# LinCorrector4.net
KiCad netlist of a schematic drawn in EAGLE
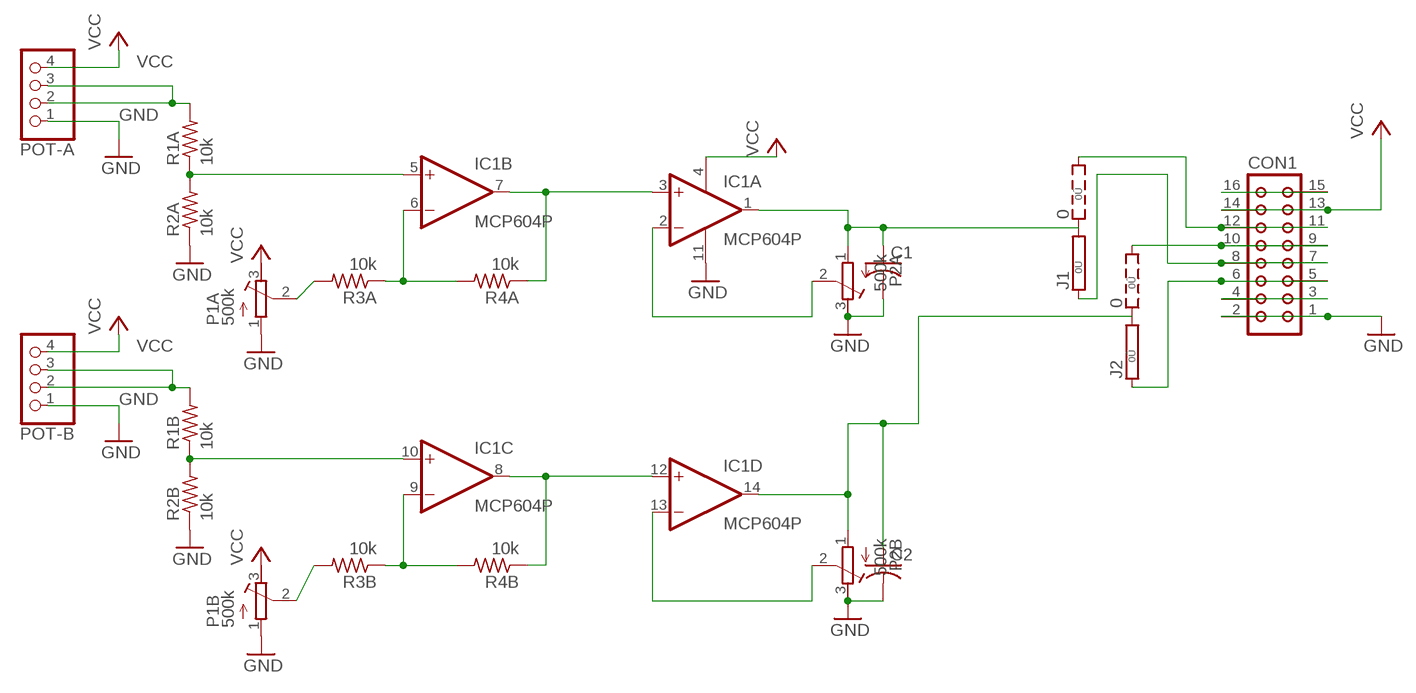
[diagram p0: schematic, sheet 1]

(export (version "E")
  (design (tool "Eeschema 10.0.6"))
  (components
    (comp (ref "C1")
      (value "C-US050-030X075")
      (footprint "eagle-import:C050-030X075")
      (libsource (lib "eagle-import") (part "C-US050-030X075"))
    )
    (comp (ref "C2")
      (value "C-US050-030X075")
      (footprint "eagle-import:C050-030X075")
      (libsource (lib "eagle-import") (part "C-US050-030X075"))
    )
    (comp (ref "CON1")
      (value "CON16")
      (footprint "eagle-import:CON16")
      (libsource (lib "eagle-import") (part "CON16"))
    )
    (comp (ref "IC1")
      (value "MCP604P")
      (footprint "eagle-import:DIL14")
      (libsource (lib "eagle-import") (part "MCP604P"))
    )
    (comp (ref "J1")
      (value "0")
      (footprint "eagle-import:0R2_10")
      (libsource (lib "eagle-import") (part "0R2"))
    )
    (comp (ref "J2")
      (value "0")
      (footprint "eagle-import:0R2_10")
      (libsource (lib "eagle-import") (part "0R2"))
    )
    (comp (ref "P1A")
      (value "500k")
      (footprint "eagle-import:RTRIM3296W")
      (libsource (lib "eagle-import") (part "R-TRIMM3296W"))
    )
    (comp (ref "P1B")
      (value "500k")
      (footprint "eagle-import:RTRIM3296W")
      (libsource (lib "eagle-import") (part "R-TRIMM3296W"))
    )
    (comp (ref "P2A")
      (value "500k")
      (footprint "eagle-import:RTRIM3296W")
      (libsource (lib "eagle-import") (part "R-TRIMM3296W"))
    )
    (comp (ref "P2B")
      (value "500k")
      (footprint "eagle-import:RTRIM3296W")
      (libsource (lib "eagle-import") (part "R-TRIMM3296W"))
    )
    (comp (ref "POT-A")
      (value "PINHD-1X4/90")
      (footprint "eagle-import:1X04_90")
      (libsource (lib "eagle-import") (part "PINHD-1X4/90"))
    )
    (comp (ref "POT-B")
      (value "PINHD-1X4/90")
      (footprint "eagle-import:1X04_90")
      (libsource (lib "eagle-import") (part "PINHD-1X4/90"))
    )
    (comp (ref "R1A")
      (value "10k")
      (footprint "eagle-import:0204_7")
      (libsource (lib "eagle-import") (part "R-US_0204/7"))
    )
    (comp (ref "R1B")
      (value "10k")
      (footprint "eagle-import:0204_7")
      (libsource (lib "eagle-import") (part "R-US_0204/7"))
    )
    (comp (ref "R2A")
      (value "10k")
      (footprint "eagle-import:0204_7")
      (libsource (lib "eagle-import") (part "R-US_0204/7"))
    )
    (comp (ref "R2B")
      (value "10k")
      (footprint "eagle-import:0204_7")
      (libsource (lib "eagle-import") (part "R-US_0204/7"))
    )
    (comp (ref "R3A")
      (value "10k")
      (footprint "eagle-import:0204_7")
      (libsource (lib "eagle-import") (part "R-US_0204/7"))
    )
    (comp (ref "R3B")
      (value "10k")
      (footprint "eagle-import:0204_7")
      (libsource (lib "eagle-import") (part "R-US_0204/7"))
    )
    (comp (ref "R4A")
      (value "10k")
      (footprint "eagle-import:0204_7")
      (libsource (lib "eagle-import") (part "R-US_0204/7"))
    )
    (comp (ref "R4B")
      (value "10k")
      (footprint "eagle-import:0204_7")
      (libsource (lib "eagle-import") (part "R-US_0204/7"))
    )
  )
  (nets
    (net (code "1") (name "GND") (class "Default")
      (node (ref "C1") (pin "2") (pinfunction "2_2") (pintype "passive"))
      (node (ref "C2") (pin "2") (pinfunction "2_2") (pintype "passive"))
      (node (ref "CON1") (pin "1") (pinfunction "1_1") (pintype "passive"))
      (node (ref "CON1") (pin "2") (pinfunction "2_2") (pintype "passive"))
      (node (ref "IC1") (pin "11") (pinfunction "V-_11") (pintype "power_in"))
      (node (ref "P1A") (pin "1") (pinfunction "A_1") (pintype "passive"))
      (node (ref "P1B") (pin "1") (pinfunction "A_1") (pintype "passive"))
      (node (ref "P2A") (pin "3") (pinfunction "E_3") (pintype "passive"))
      (node (ref "P2B") (pin "3") (pinfunction "E_3") (pintype "passive"))
      (node (ref "POT-A") (pin "1") (pinfunction "1_1") (pintype "passive"))
      (node (ref "POT-B") (pin "1") (pinfunction "1_1") (pintype "passive"))
      (node (ref "R2A") (pin "1") (pinfunction "1_1") (pintype "passive"))
      (node (ref "R2B") (pin "1") (pinfunction "1_1") (pintype "passive"))
    )
    (net (code "2") (name "Net-(CON1-Pad3)") (class "Default")
      (node (ref "CON1") (pin "3") (pinfunction "3_3") (pintype "passive"))
      (node (ref "CON1") (pin "4") (pinfunction "4_4") (pintype "passive"))
    )
    (net (code "3") (name "Net-(CON1-Pad5)") (class "Default")
      (node (ref "CON1") (pin "5") (pinfunction "5_5") (pintype "passive"))
      (node (ref "CON1") (pin "6") (pinfunction "6_6") (pintype "passive"))
      (node (ref "J2") (pin "1") (pinfunction "1_1") (pintype "passive"))
    )
    (net (code "4") (name "Net-(CON1-Pad7)") (class "Default")
      (node (ref "CON1") (pin "7") (pinfunction "7_7") (pintype "passive"))
      (node (ref "CON1") (pin "8") (pinfunction "8_8") (pintype "passive"))
      (node (ref "J1") (pin "1") (pinfunction "1_1") (pintype "passive"))
    )
    (net (code "5") (name "Net-(CON1-Pad10)") (class "Default")
      (node (ref "CON1") (pin "10") (pinfunction "10_10") (pintype "passive"))
      (node (ref "CON1") (pin "9") (pinfunction "9_9") (pintype "passive"))
      (node (ref "J2") (pin "3") (pinfunction "3_3") (pintype "passive"))
    )
    (net (code "6") (name "Net-(CON1-Pad11)") (class "Default")
      (node (ref "CON1") (pin "11") (pinfunction "11_11") (pintype "passive"))
      (node (ref "CON1") (pin "12") (pinfunction "12_12") (pintype "passive"))
      (node (ref "J1") (pin "3") (pinfunction "3_3") (pintype "passive"))
    )
    (net (code "7") (name "Net-(CON1-Pad15)") (class "Default")
      (node (ref "CON1") (pin "15") (pinfunction "15_15") (pintype "passive"))
      (node (ref "CON1") (pin "16") (pinfunction "16_16") (pintype "passive"))
    )
    (net (code "8") (name "Net-(IC1A-+IN)") (class "Default")
      (node (ref "IC1") (pin "3") (pinfunction "+IN_3") (pintype "input"))
      (node (ref "IC1") (pin "7") (pinfunction "OUT_7") (pintype "output"))
      (node (ref "R4A") (pin "1") (pinfunction "1_1") (pintype "passive"))
    )
    (net (code "9") (name "Net-(IC1A--IN)") (class "Default")
      (node (ref "IC1") (pin "2") (pinfunction "-IN_2") (pintype "input"))
      (node (ref "P2A") (pin "2") (pinfunction "S_2") (pintype "passive"))
    )
    (net (code "10") (name "Net-(IC1A-OUT)") (class "Default")
      (node (ref "C1") (pin "1") (pinfunction "1_1") (pintype "passive"))
      (node (ref "IC1") (pin "1") (pinfunction "OUT_1") (pintype "output"))
      (node (ref "J1") (pin "2") (pinfunction "2_2") (pintype "passive"))
      (node (ref "P2A") (pin "1") (pinfunction "A_1") (pintype "passive"))
    )
    (net (code "11") (name "Net-(IC1B-+IN)") (class "Default")
      (node (ref "IC1") (pin "5") (pinfunction "+IN_5") (pintype "input"))
      (node (ref "R1A") (pin "1") (pinfunction "1_1") (pintype "passive"))
      (node (ref "R2A") (pin "2") (pinfunction "2_2") (pintype "passive"))
    )
    (net (code "12") (name "Net-(IC1B--IN)") (class "Default")
      (node (ref "IC1") (pin "6") (pinfunction "-IN_6") (pintype "input"))
      (node (ref "R3A") (pin "1") (pinfunction "1_1") (pintype "passive"))
      (node (ref "R4A") (pin "2") (pinfunction "2_2") (pintype "passive"))
    )
    (net (code "13") (name "Net-(IC1C-+IN)") (class "Default")
      (node (ref "IC1") (pin "10") (pinfunction "+IN_10") (pintype "input"))
      (node (ref "R1B") (pin "1") (pinfunction "1_1") (pintype "passive"))
      (node (ref "R2B") (pin "2") (pinfunction "2_2") (pintype "passive"))
    )
    (net (code "14") (name "Net-(IC1C--IN)") (class "Default")
      (node (ref "IC1") (pin "9") (pinfunction "-IN_9") (pintype "input"))
      (node (ref "R3B") (pin "1") (pinfunction "1_1") (pintype "passive"))
      (node (ref "R4B") (pin "2") (pinfunction "2_2") (pintype "passive"))
    )
    (net (code "15") (name "Net-(IC1C-OUT)") (class "Default")
      (node (ref "IC1") (pin "12") (pinfunction "+IN_12") (pintype "input"))
      (node (ref "IC1") (pin "8") (pinfunction "OUT_8") (pintype "output"))
      (node (ref "R4B") (pin "1") (pinfunction "1_1") (pintype "passive"))
    )
    (net (code "16") (name "Net-(IC1D--IN)") (class "Default")
      (node (ref "IC1") (pin "13") (pinfunction "-IN_13") (pintype "input"))
      (node (ref "P2B") (pin "2") (pinfunction "S_2") (pintype "passive"))
    )
    (net (code "17") (name "Net-(IC1D-OUT)") (class "Default")
      (node (ref "C2") (pin "1") (pinfunction "1_1") (pintype "passive"))
      (node (ref "IC1") (pin "14") (pinfunction "OUT_14") (pintype "output"))
      (node (ref "J2") (pin "2") (pinfunction "2_2") (pintype "passive"))
      (node (ref "P2B") (pin "1") (pinfunction "A_1") (pintype "passive"))
    )
    (net (code "18") (name "Net-(P1A-S)") (class "Default")
      (node (ref "P1A") (pin "2") (pinfunction "S_2") (pintype "passive"))
      (node (ref "R3A") (pin "2") (pinfunction "2_2") (pintype "passive"))
    )
    (net (code "19") (name "Net-(P1B-S)") (class "Default")
      (node (ref "P1B") (pin "2") (pinfunction "S_2") (pintype "passive"))
      (node (ref "R3B") (pin "2") (pinfunction "2_2") (pintype "passive"))
    )
    (net (code "20") (name "Net-(POT-A-Pad2)") (class "Default")
      (node (ref "POT-A") (pin "2") (pinfunction "2_2") (pintype "passive"))
      (node (ref "POT-A") (pin "3") (pinfunction "3_3") (pintype "passive"))
      (node (ref "R1A") (pin "2") (pinfunction "2_2") (pintype "passive"))
    )
    (net (code "21") (name "Net-(POT-B-Pad2)") (class "Default")
      (node (ref "POT-B") (pin "2") (pinfunction "2_2") (pintype "passive"))
      (node (ref "POT-B") (pin "3") (pinfunction "3_3") (pintype "passive"))
      (node (ref "R1B") (pin "2") (pinfunction "2_2") (pintype "passive"))
    )
    (net (code "22") (name "VCC") (class "Default")
      (node (ref "CON1") (pin "13") (pinfunction "13_13") (pintype "passive"))
      (node (ref "CON1") (pin "14") (pinfunction "14_14") (pintype "passive"))
      (node (ref "IC1") (pin "4") (pinfunction "V+_4") (pintype "power_in"))
      (node (ref "P1A") (pin "3") (pinfunction "E_3") (pintype "passive"))
      (node (ref "P1B") (pin "3") (pinfunction "E_3") (pintype "passive"))
      (node (ref "POT-A") (pin "4") (pinfunction "4_4") (pintype "passive"))
      (node (ref "POT-B") (pin "4") (pinfunction "4_4") (pintype "passive"))
    )
  )
)
